# XStepper_Opto-Isolator_ADuM1301_v001.net
KiCad netlist of a schematic drawn in EAGLE
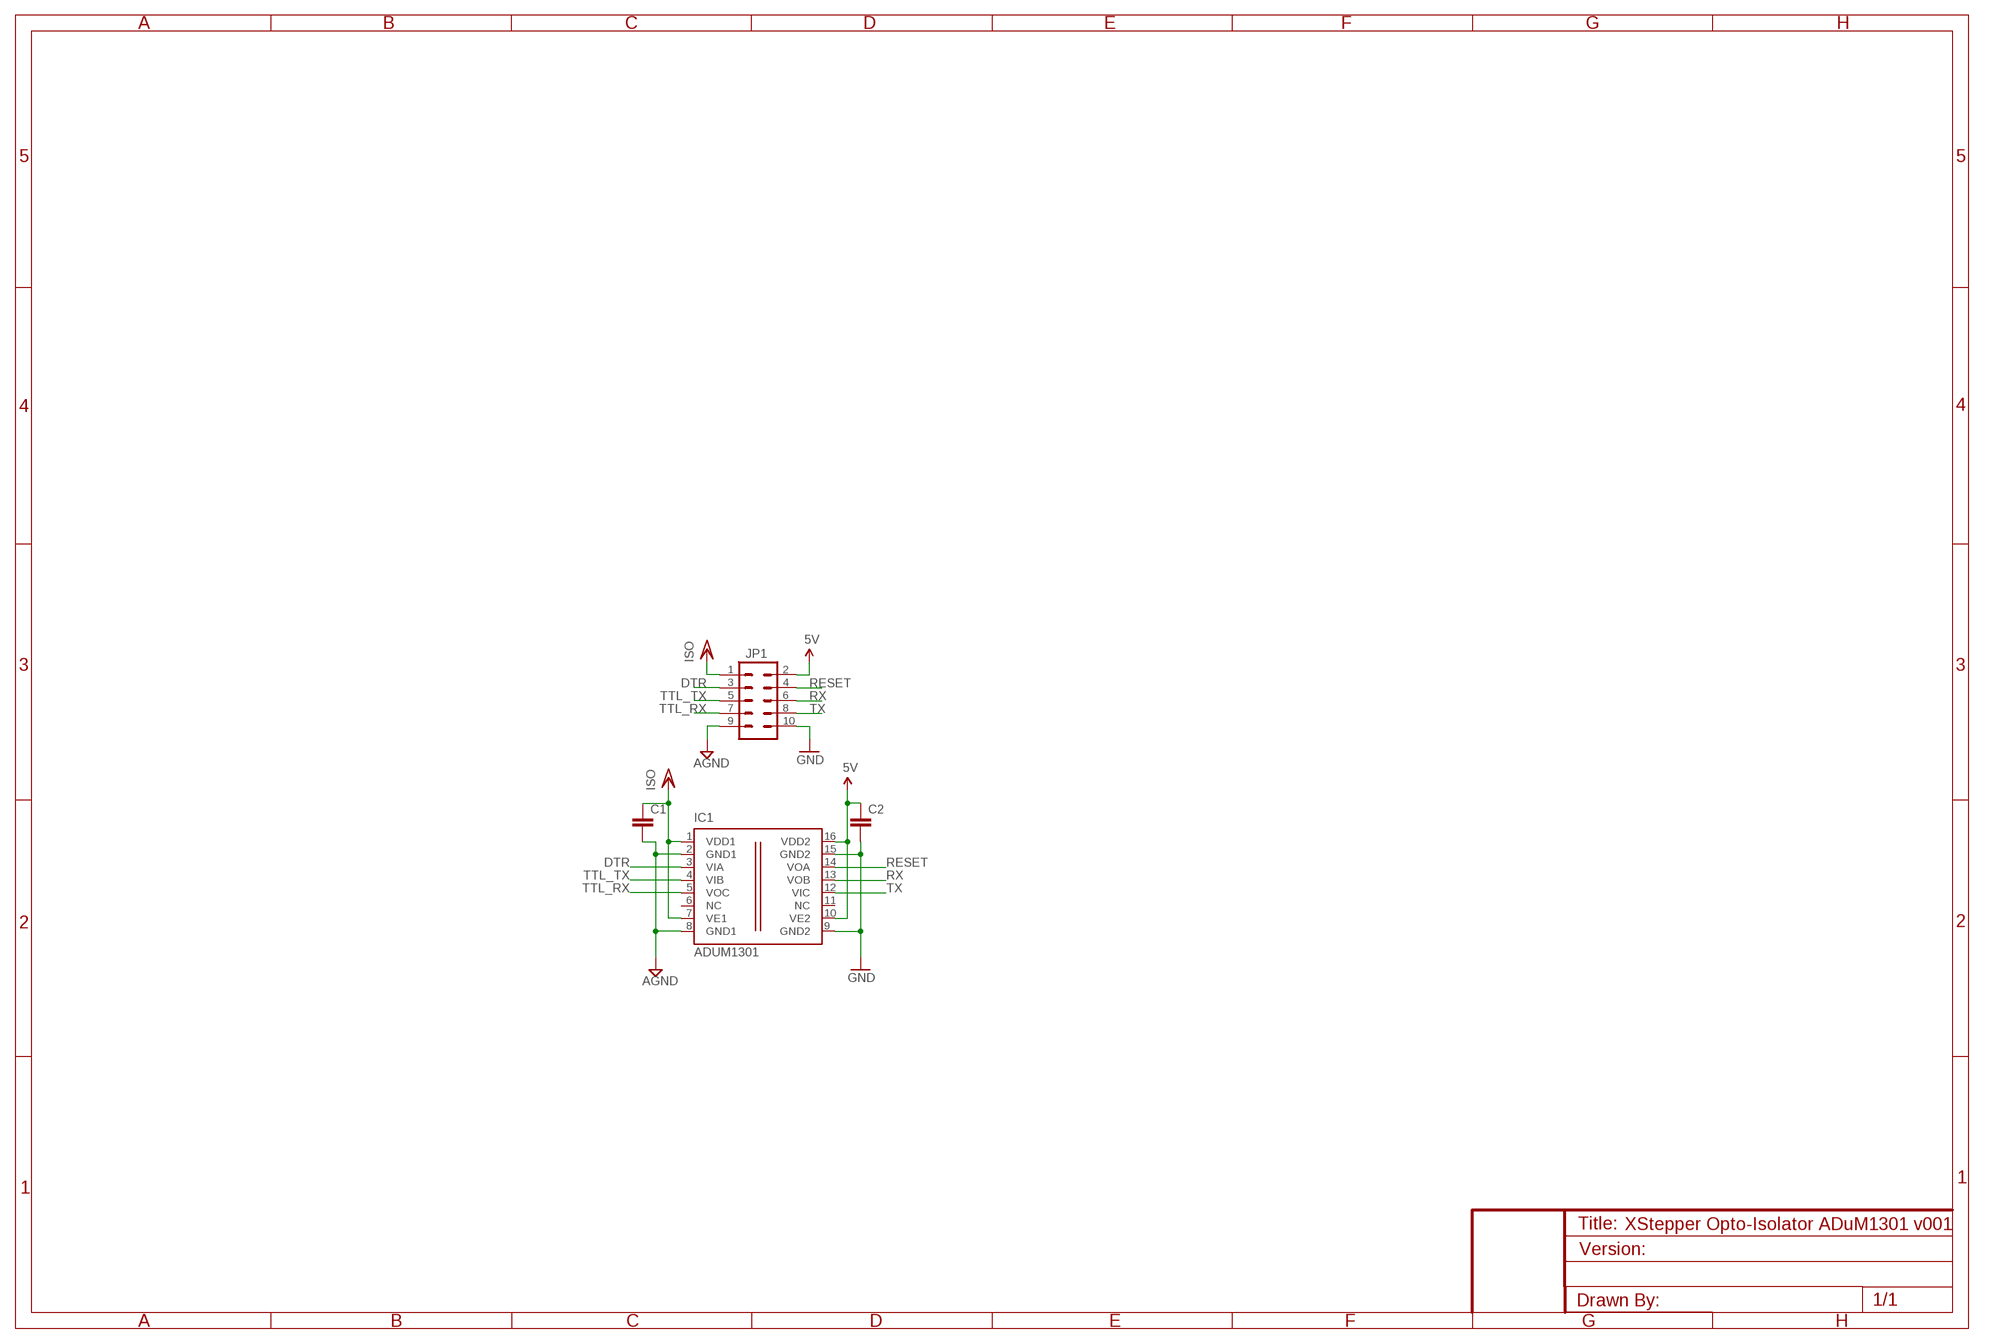
[diagram p0: schematic, sheet 1]

(export (version "E")
  (design (tool "Eeschema 10.0.6"))
  (components
    (comp (ref "C1")
      (value "CAP0805")
      (footprint "eagle-import:0805")
      (libsource (lib "eagle-import") (part "CAP0805"))
    )
    (comp (ref "C2")
      (value "CAP0805")
      (footprint "eagle-import:0805")
      (libsource (lib "eagle-import") (part "CAP0805"))
    )
    (comp (ref "IC1")
      (value "ADUM1301")
      (footprint "eagle-import:SO-16W")
      (fields (field (name "MPN") "ADUM1301BRWZ"))
      (libsource (lib "eagle-import") (part "ADUM1301"))
    )
    (comp (ref "JP1")
      (value "M05X2PTH")
      (footprint "eagle-import:AVR_ICSP")
      (libsource (lib "eagle-import") (part "M05X2PTH"))
    )
  )
  (nets
    (net (code "1") (name "/DTR") (class "Default")
      (node (ref "IC1") (pin "3") (pinfunction "VIA_3") (pintype "input"))
      (node (ref "JP1") (pin "3") (pinfunction "3_3") (pintype "passive"))
    )
    (net (code "2") (name "/RESET") (class "Default")
      (node (ref "IC1") (pin "14") (pinfunction "VOA_14") (pintype "tri_state"))
      (node (ref "JP1") (pin "4") (pinfunction "4_4") (pintype "passive"))
    )
    (net (code "3") (name "/RX") (class "Default")
      (node (ref "IC1") (pin "13") (pinfunction "VOB_13") (pintype "tri_state"))
      (node (ref "JP1") (pin "6") (pinfunction "6_6") (pintype "passive"))
    )
    (net (code "4") (name "/TTL_RX") (class "Default")
      (node (ref "IC1") (pin "5") (pinfunction "VOC_5") (pintype "tri_state"))
      (node (ref "JP1") (pin "7") (pinfunction "7_7") (pintype "passive"))
    )
    (net (code "5") (name "/TTL_TX") (class "Default")
      (node (ref "IC1") (pin "4") (pinfunction "VIB_4") (pintype "input"))
      (node (ref "JP1") (pin "5") (pinfunction "5_5") (pintype "passive"))
    )
    (net (code "6") (name "/TX") (class "Default")
      (node (ref "IC1") (pin "12") (pinfunction "VIC_12") (pintype "input"))
      (node (ref "JP1") (pin "8") (pinfunction "8_8") (pintype "passive"))
    )
    (net (code "7") (name "5V") (class "Default")
      (node (ref "C2") (pin "1") (pinfunction "1_1") (pintype "passive"))
      (node (ref "IC1") (pin "10") (pinfunction "VE2_10") (pintype "input"))
      (node (ref "IC1") (pin "16") (pinfunction "VDD2_16") (pintype "input"))
      (node (ref "JP1") (pin "2") (pinfunction "2_2") (pintype "passive"))
    )
    (net (code "8") (name "AGND") (class "Default")
      (node (ref "C1") (pin "2") (pinfunction "2_2") (pintype "passive"))
      (node (ref "IC1") (pin "2") (pinfunction "GND1_2") (pintype "input"))
      (node (ref "IC1") (pin "8") (pinfunction "GND1_8") (pintype "input"))
      (node (ref "JP1") (pin "9") (pinfunction "9_9") (pintype "passive"))
    )
    (net (code "9") (name "GND") (class "Default")
      (node (ref "C2") (pin "2") (pinfunction "2_2") (pintype "passive"))
      (node (ref "IC1") (pin "15") (pinfunction "GND2_15") (pintype "input"))
      (node (ref "IC1") (pin "9") (pinfunction "GND2_9") (pintype "input"))
      (node (ref "JP1") (pin "10") (pinfunction "10_10") (pintype "passive"))
    )
    (net (code "10") (name "ISO") (class "Default")
      (node (ref "C1") (pin "1") (pinfunction "1_1") (pintype "passive"))
      (node (ref "IC1") (pin "1") (pinfunction "VDD1_1") (pintype "input"))
      (node (ref "IC1") (pin "7") (pinfunction "VE1_7") (pintype "input"))
      (node (ref "JP1") (pin "1") (pinfunction "1_1") (pintype "passive"))
    )
    (net (code "11") (name "unconnected-(IC1-NC-Pad6)") (class "Default")
      (node (ref "IC1") (pin "6") (pinfunction "NC_6") (pintype "no_connect"))
    )
    (net (code "12") (name "unconnected-(IC1-NC-Pad11)") (class "Default")
      (node (ref "IC1") (pin "11") (pinfunction "NC_11") (pintype "no_connect"))
    )
  )
)
